# 1-Schematic_Placa_Final_ALS.net
KiCad netlist of a schematic drawn in EasyEDA
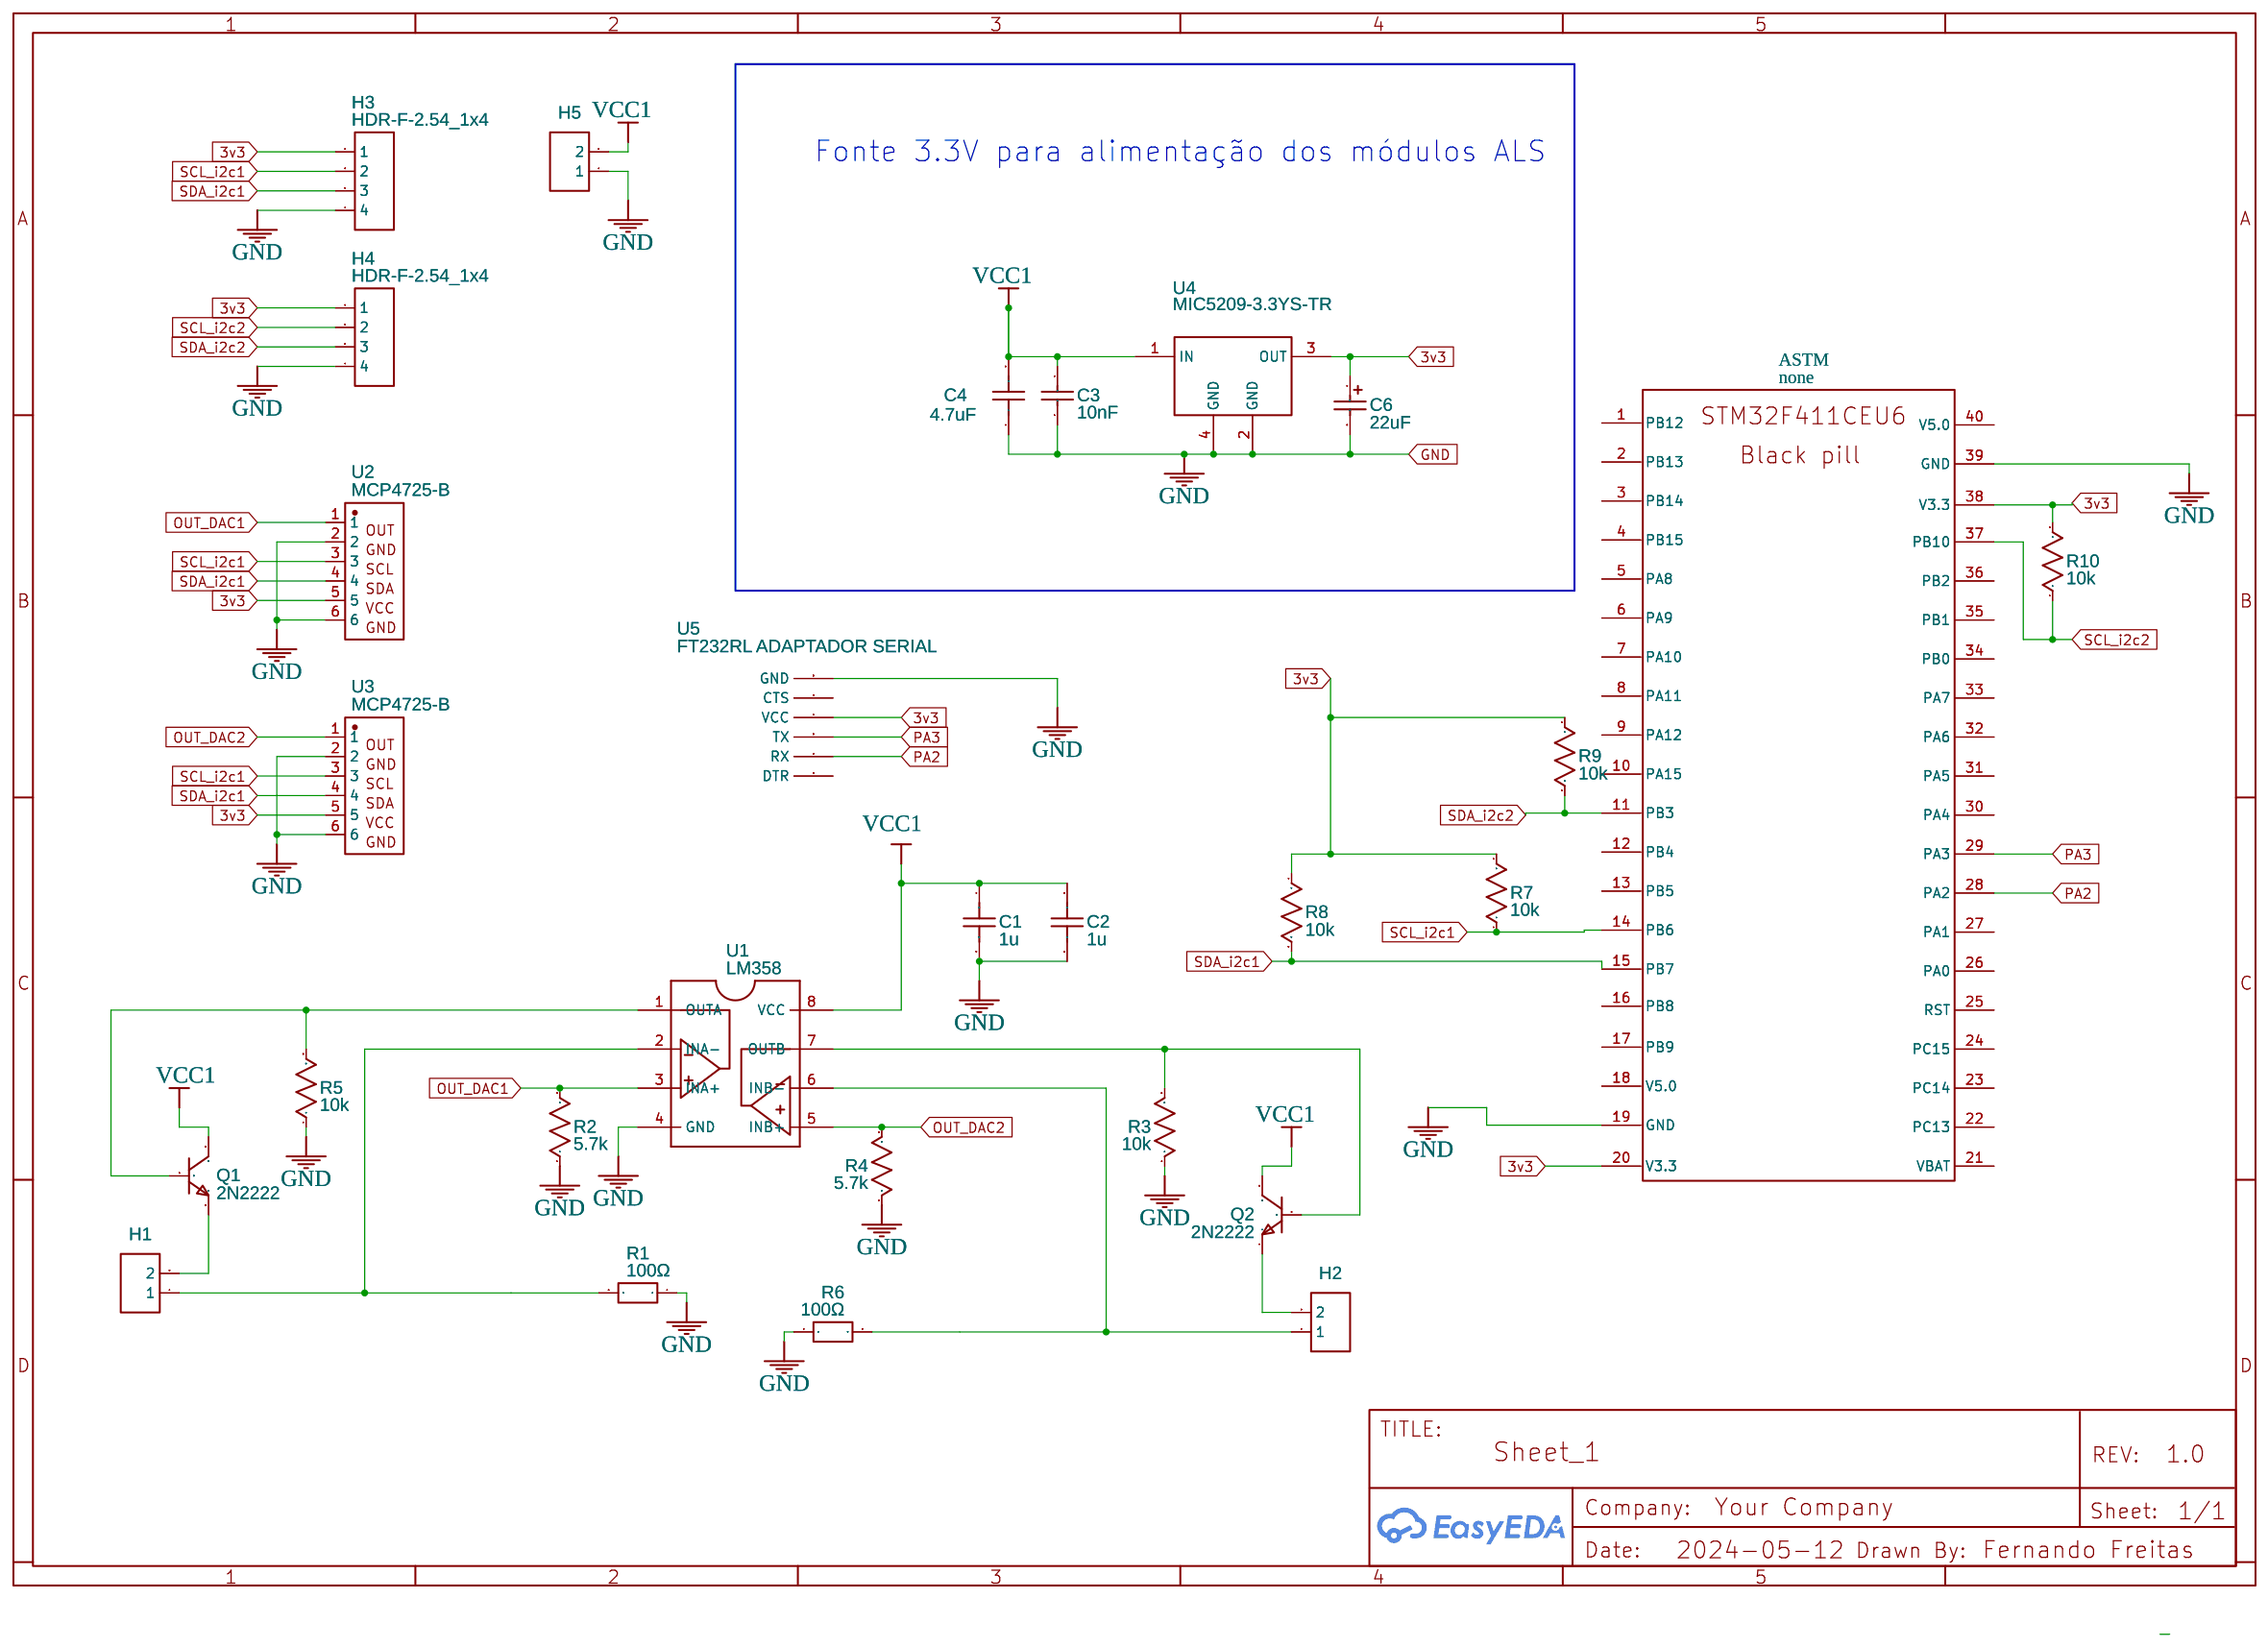
[diagram p0: schematic sheet]

(export (version "E")
  (design (tool "Eeschema 10.0.6"))
  (components
    (comp (ref "ASTM") (value "none") (libsource (lib "") (part "Unknown_912_-407")))
    (comp (ref "C1") (value "1u") (libsource (lib "") (part "C_RAD-0.3_US")))
    (comp (ref "C2") (value "1u") (libsource (lib "") (part "C_RAD-0.3_US")))
    (comp (ref "C3")
      (value "10nF")
      (fields
        (field (name "Manufacturer Part") "CL21B103KBANNNC")
        (field (name "Manufacturer") "SAMSUNG(三星)")
      )
      (libsource (lib "") (part "CL21B103KBANNNC"))
    )
    (comp (ref "C4")
      (value "4.7uF")
      (fields (field (name "Manufacturer Part") "CGA3E2X8R1E104M080AA") (field (name "Manufacturer") "TDK"))
      (libsource (lib "") (part "CGA3E2X8R1E104M080 AA"))
    )
    (comp (ref "C6")
      (value "22uF")
      (fields (field (name "Manufacturer Part") "TAJB226K016RNJ") (field (name "Manufacturer") "Kyocera AVX"))
      (libsource (lib "") (part "TAJB226K016RNJ"))
    )
    (comp (ref "H1") (value "HDR-F-2.54_1x2") (libsource (lib "") (part "HDR-F-2.54_1x2")))
    (comp (ref "H2") (value "HDR-F-2.54_1x2") (libsource (lib "") (part "HDR-F-2.54_1x2_1")))
    (comp (ref "H3") (value "HDR-F-2.54_1x4") (libsource (lib "") (part "HDR-F-2.54_1x4")))
    (comp (ref "H4") (value "HDR-F-2.54_1x4") (libsource (lib "") (part "HDR-F-2.54_1x4")))
    (comp (ref "H5") (value "HDR-F-2.54_1x2") (libsource (lib "") (part "HDR-F-2.54_1x2")))
    (comp (ref "Q1")
      (value "2N2222")
      (fields (field (name "Manufacturer Part") "2N2222A") (field (name "Manufacturer") "ST(先科)"))
      (libsource (lib "") (part "2N2222"))
    )
    (comp (ref "Q2")
      (value "2N2222")
      (fields (field (name "Manufacturer Part") "2N2222A") (field (name "Manufacturer") "ST(先科)"))
      (libsource (lib "") (part "2N2222_1"))
    )
    (comp (ref "R1")
      (value "100Ω")
      (fields
        (field (name "Manufacturer Part") "RN 1/4W 100R F T/B A1")
        (field (name "Manufacturer") "Tyohm(幸亚电阻)")
      )
      (libsource (lib "") (part "100R 1/4W_1"))
    )
    (comp (ref "R2") (value "5.7k") (libsource (lib "") (part "R_AXIAL-0.3_US")))
    (comp (ref "R3") (value "10k") (libsource (lib "") (part "R_AXIAL-0.3_US_1")))
    (comp (ref "R4") (value "5.7k") (libsource (lib "") (part "R_AXIAL-0.3_US_1")))
    (comp (ref "R5") (value "10k") (libsource (lib "") (part "R_AXIAL-0.3_US")))
    (comp (ref "R6")
      (value "100Ω")
      (fields
        (field (name "Manufacturer Part") "RN 1/4W 100R F T/B A1")
        (field (name "Manufacturer") "Tyohm(幸亚电阻)")
      )
      (libsource (lib "") (part "100R 1/4W"))
    )
    (comp (ref "R7") (value "10k") (libsource (lib "") (part "R_AXIAL-0.3_US")))
    (comp (ref "R8") (value "10k") (libsource (lib "") (part "R_AXIAL-0.3_US_2")))
    (comp (ref "R9") (value "10k") (libsource (lib "") (part "R_AXIAL-0.3_US_2")))
    (comp (ref "R10") (value "10k") (libsource (lib "") (part "R_AXIAL-0.3_US")))
    (comp (ref "U1")
      (value "LM358")
      (fields (field (name "Manufacturer Part") "TI") (field (name "Manufacturer") "LM358MX/NOPB"))
      (libsource (lib "") (part "LM358"))
    )
    (comp (ref "U2")
      (value "MCP4725-B")
      (fields
        (field (name "Manufacturer Part") "A2005WV-6P")
        (field (name "Manufacturer") "Changjiang Connectors")
      )
      (libsource (lib "") (part "MCP4725-B"))
    )
    (comp (ref "U3")
      (value "MCP4725-B")
      (fields
        (field (name "Manufacturer Part") "A2005WV-6P")
        (field (name "Manufacturer") "Changjiang Connectors")
      )
      (libsource (lib "") (part "MCP4725-B"))
    )
    (comp (ref "U4")
      (value "MIC5209-3.3YS-TR")
      (fields
        (field (name "Manufacturer Part") "TLE42744GSV33")
        (field (name "Manufacturer") "Infineon(英飞凌)")
      )
      (libsource (lib "") (part "TLE42744GSV33"))
    )
    (comp (ref "U5")
      (value "FT232RL ADAPTADOR SERIAL")
      (fields (field (name "Manufacturer Part") "WILSON") (field (name "Manufacturer") "WILSON PEREZ"))
      (libsource (lib "") (part "FT232RL ADAPTADOR SERIAL"))
    )
  )
  (nets
    (net (code "1") (name "3v3") (class "Default")
      (node (ref "ASTM") (pin "20") (pinfunction "V3.3_20") (pintype "passive"))
      (node (ref "ASTM") (pin "38") (pinfunction "V3.3_38") (pintype "passive"))
      (node (ref "C6") (pin "1") (pinfunction "1_1") (pintype "input"))
      (node (ref "H3") (pin "1") (pinfunction "1_1") (pintype "unspecified"))
      (node (ref "H4") (pin "1") (pinfunction "1_1") (pintype "unspecified"))
      (node (ref "R10") (pin "2") (pinfunction "2_2") (pintype "unspecified"))
      (node (ref "R7") (pin "2") (pinfunction "2_2") (pintype "unspecified"))
      (node (ref "R8") (pin "1") (pinfunction "1_1") (pintype "unspecified"))
      (node (ref "R9") (pin "1") (pinfunction "1_1") (pintype "unspecified"))
      (node (ref "U2") (pin "5") (pinfunction "5_5") (pintype "unspecified"))
      (node (ref "U3") (pin "5") (pinfunction "5_5") (pintype "unspecified"))
      (node (ref "U4") (pin "3") (pinfunction "OUT_3") (pintype "unspecified"))
      (node (ref "U5") (pin "4") (pinfunction "VCC_4") (pintype "unspecified"))
    )
    (net (code "2") (name "GND") (class "Default")
      (node (ref "ASTM") (pin "19") (pinfunction "GND_19") (pintype "passive"))
      (node (ref "ASTM") (pin "39") (pinfunction "GND_39") (pintype "passive"))
      (node (ref "C1") (pin "2") (pinfunction "2_2") (pintype "unspecified"))
      (node (ref "C2") (pin "2") (pinfunction "2_2") (pintype "unspecified"))
      (node (ref "C3") (pin "1") (pinfunction "1_1") (pintype "input"))
      (node (ref "C4") (pin "1") (pinfunction "1_1") (pintype "unspecified"))
      (node (ref "C6") (pin "2") (pinfunction "2_2") (pintype "input"))
      (node (ref "H3") (pin "4") (pinfunction "4_4") (pintype "unspecified"))
      (node (ref "H4") (pin "4") (pinfunction "4_4") (pintype "unspecified"))
      (node (ref "H5") (pin "1") (pinfunction "1_1") (pintype "input"))
      (node (ref "R1") (pin "1") (pinfunction "1_1") (pintype "unspecified"))
      (node (ref "R2") (pin "1") (pinfunction "1_1") (pintype "unspecified"))
      (node (ref "R3") (pin "1") (pinfunction "1_1") (pintype "unspecified"))
      (node (ref "R4") (pin "1") (pinfunction "1_1") (pintype "unspecified"))
      (node (ref "R5") (pin "1") (pinfunction "1_1") (pintype "unspecified"))
      (node (ref "R6") (pin "1") (pinfunction "1_1") (pintype "unspecified"))
      (node (ref "U1") (pin "4") (pinfunction "GND_4") (pintype "unspecified"))
      (node (ref "U2") (pin "2") (pinfunction "2_2") (pintype "unspecified"))
      (node (ref "U2") (pin "6") (pinfunction "6_6") (pintype "unspecified"))
      (node (ref "U3") (pin "2") (pinfunction "2_2") (pintype "unspecified"))
      (node (ref "U3") (pin "6") (pinfunction "6_6") (pintype "unspecified"))
      (node (ref "U4") (pin "2") (pinfunction "GND_2") (pintype "unspecified"))
      (node (ref "U4") (pin "4") (pinfunction "GND_4") (pintype "unspecified"))
      (node (ref "U5") (pin "6") (pinfunction "GND_6") (pintype "unspecified"))
    )
    (net (code "3") (name "Net-(Q1-B)") (class "Default")
      (node (ref "Q1") (pin "2") (pinfunction "B_2") (pintype "unspecified"))
      (node (ref "R5") (pin "2") (pinfunction "2_2") (pintype "unspecified"))
      (node (ref "U1") (pin "1") (pinfunction "OUTA_1") (pintype "output"))
    )
    (net (code "4") (name "Net-(Q1-E)") (class "Default")
      (node (ref "H1") (pin "2") (pinfunction "2_2") (pintype "input"))
      (node (ref "Q1") (pin "1") (pinfunction "E_1") (pintype "unspecified"))
    )
    (net (code "5") (name "Net-(Q2-B)") (class "Default")
      (node (ref "Q2") (pin "2") (pinfunction "B_2") (pintype "unspecified"))
      (node (ref "R3") (pin "2") (pinfunction "2_2") (pintype "unspecified"))
      (node (ref "U1") (pin "7") (pinfunction "OUTB_7") (pintype "unspecified"))
    )
    (net (code "6") (name "Net-(Q2-E)") (class "Default")
      (node (ref "H2") (pin "2") (pinfunction "2_2") (pintype "input"))
      (node (ref "Q2") (pin "1") (pinfunction "E_1") (pintype "unspecified"))
    )
    (net (code "7") (name "Net-(U1-INA-)") (class "Default")
      (node (ref "H1") (pin "1") (pinfunction "1_1") (pintype "input"))
      (node (ref "R1") (pin "2") (pinfunction "2_2") (pintype "unspecified"))
      (node (ref "U1") (pin "2") (pinfunction "INA-_2") (pintype "unspecified"))
    )
    (net (code "8") (name "Net-(U1-INB-)") (class "Default")
      (node (ref "H2") (pin "1") (pinfunction "1_1") (pintype "input"))
      (node (ref "R6") (pin "2") (pinfunction "2_2") (pintype "unspecified"))
      (node (ref "U1") (pin "6") (pinfunction "INB-_6") (pintype "unspecified"))
    )
    (net (code "9") (name "OUT_DAC1") (class "Default")
      (node (ref "R2") (pin "2") (pinfunction "2_2") (pintype "unspecified"))
      (node (ref "U1") (pin "3") (pinfunction "INA+_3") (pintype "unspecified"))
      (node (ref "U2") (pin "1") (pinfunction "1_1") (pintype "unspecified"))
    )
    (net (code "10") (name "OUT_DAC2") (class "Default")
      (node (ref "R4") (pin "2") (pinfunction "2_2") (pintype "unspecified"))
      (node (ref "U1") (pin "5") (pinfunction "INB+_5") (pintype "unspecified"))
      (node (ref "U3") (pin "1") (pinfunction "1_1") (pintype "unspecified"))
    )
    (net (code "11") (name "PA2") (class "Default")
      (node (ref "ASTM") (pin "28") (pinfunction "PA2_28") (pintype "unspecified"))
      (node (ref "U5") (pin "2") (pinfunction "RX_2") (pintype "unspecified"))
    )
    (net (code "12") (name "PA3") (class "Default")
      (node (ref "ASTM") (pin "29") (pinfunction "PA3_29") (pintype "unspecified"))
      (node (ref "U5") (pin "3") (pinfunction "TX_3") (pintype "unspecified"))
    )
    (net (code "13") (name "SCL_i2c1") (class "Default")
      (node (ref "ASTM") (pin "14") (pinfunction "PB6_14") (pintype "unspecified"))
      (node (ref "H3") (pin "2") (pinfunction "2_2") (pintype "unspecified"))
      (node (ref "R7") (pin "1") (pinfunction "1_1") (pintype "unspecified"))
      (node (ref "U2") (pin "3") (pinfunction "3_3") (pintype "unspecified"))
      (node (ref "U3") (pin "3") (pinfunction "3_3") (pintype "unspecified"))
    )
    (net (code "14") (name "SCL_i2c2") (class "Default")
      (node (ref "ASTM") (pin "37") (pinfunction "PB10_37") (pintype "unspecified"))
      (node (ref "H4") (pin "2") (pinfunction "2_2") (pintype "unspecified"))
      (node (ref "R10") (pin "1") (pinfunction "1_1") (pintype "unspecified"))
    )
    (net (code "15") (name "SDA_i2c1") (class "Default")
      (node (ref "ASTM") (pin "15") (pinfunction "PB7_15") (pintype "unspecified"))
      (node (ref "H3") (pin "3") (pinfunction "3_3") (pintype "unspecified"))
      (node (ref "R8") (pin "2") (pinfunction "2_2") (pintype "unspecified"))
      (node (ref "U2") (pin "4") (pinfunction "4_4") (pintype "unspecified"))
      (node (ref "U3") (pin "4") (pinfunction "4_4") (pintype "unspecified"))
    )
    (net (code "16") (name "SDA_i2c2") (class "Default")
      (node (ref "ASTM") (pin "11") (pinfunction "PB3_11") (pintype "unspecified"))
      (node (ref "H4") (pin "3") (pinfunction "3_3") (pintype "unspecified"))
      (node (ref "R9") (pin "2") (pinfunction "2_2") (pintype "unspecified"))
    )
    (net (code "17") (name "VCC1") (class "Default")
      (node (ref "C1") (pin "1") (pinfunction "1_1") (pintype "unspecified"))
      (node (ref "C2") (pin "1") (pinfunction "1_1") (pintype "unspecified"))
      (node (ref "C3") (pin "2") (pinfunction "2_2") (pintype "input"))
      (node (ref "C4") (pin "2") (pinfunction "2_2") (pintype "unspecified"))
      (node (ref "H5") (pin "2") (pinfunction "2_2") (pintype "input"))
      (node (ref "Q1") (pin "3") (pinfunction "C_3") (pintype "unspecified"))
      (node (ref "Q2") (pin "3") (pinfunction "C_3") (pintype "unspecified"))
      (node (ref "U1") (pin "8") (pinfunction "VCC_8") (pintype "unspecified"))
      (node (ref "U4") (pin "1") (pinfunction "IN_1") (pintype "unspecified"))
    )
    (net (code "18") (name "unconnected-(ASTM-PA0-Pad26)") (class "Default")
      (node (ref "ASTM") (pin "26") (pinfunction "PA0_26") (pintype "unspecified"))
    )
    (net (code "19") (name "unconnected-(ASTM-PA1-Pad27)") (class "Default")
      (node (ref "ASTM") (pin "27") (pinfunction "PA1_27") (pintype "unspecified"))
    )
    (net (code "20") (name "unconnected-(ASTM-PA4-Pad30)") (class "Default")
      (node (ref "ASTM") (pin "30") (pinfunction "PA4_30") (pintype "unspecified"))
    )
    (net (code "21") (name "unconnected-(ASTM-PA5-Pad31)") (class "Default")
      (node (ref "ASTM") (pin "31") (pinfunction "PA5_31") (pintype "unspecified"))
    )
    (net (code "22") (name "unconnected-(ASTM-PA6-Pad32)") (class "Default")
      (node (ref "ASTM") (pin "32") (pinfunction "PA6_32") (pintype "unspecified"))
    )
    (net (code "23") (name "unconnected-(ASTM-PA7-Pad33)") (class "Default")
      (node (ref "ASTM") (pin "33") (pinfunction "PA7_33") (pintype "unspecified"))
    )
    (net (code "24") (name "unconnected-(ASTM-PA8-Pad5)") (class "Default")
      (node (ref "ASTM") (pin "5") (pinfunction "PA8_5") (pintype "unspecified"))
    )
    (net (code "25") (name "unconnected-(ASTM-PA9-Pad6)") (class "Default")
      (node (ref "ASTM") (pin "6") (pinfunction "PA9_6") (pintype "unspecified"))
    )
    (net (code "26") (name "unconnected-(ASTM-PA10-Pad7)") (class "Default")
      (node (ref "ASTM") (pin "7") (pinfunction "PA10_7") (pintype "unspecified"))
    )
    (net (code "27") (name "unconnected-(ASTM-PA11-Pad8)") (class "Default")
      (node (ref "ASTM") (pin "8") (pinfunction "PA11_8") (pintype "unspecified"))
    )
    (net (code "28") (name "unconnected-(ASTM-PA12-Pad9)") (class "Default")
      (node (ref "ASTM") (pin "9") (pinfunction "PA12_9") (pintype "unspecified"))
    )
    (net (code "29") (name "unconnected-(ASTM-PA15-Pad10)") (class "Default")
      (node (ref "ASTM") (pin "10") (pinfunction "PA15_10") (pintype "unspecified"))
    )
    (net (code "30") (name "unconnected-(ASTM-PB0-Pad34)") (class "Default")
      (node (ref "ASTM") (pin "34") (pinfunction "PB0_34") (pintype "unspecified"))
    )
    (net (code "31") (name "unconnected-(ASTM-PB1-Pad35)") (class "Default")
      (node (ref "ASTM") (pin "35") (pinfunction "PB1_35") (pintype "unspecified"))
    )
    (net (code "32") (name "unconnected-(ASTM-PB2-Pad36)") (class "Default")
      (node (ref "ASTM") (pin "36") (pinfunction "PB2_36") (pintype "unspecified"))
    )
    (net (code "33") (name "unconnected-(ASTM-PB4-Pad12)") (class "Default")
      (node (ref "ASTM") (pin "12") (pinfunction "PB4_12") (pintype "unspecified"))
    )
    (net (code "34") (name "unconnected-(ASTM-PB5-Pad13)") (class "Default")
      (node (ref "ASTM") (pin "13") (pinfunction "PB5_13") (pintype "unspecified"))
    )
    (net (code "35") (name "unconnected-(ASTM-PB8-Pad16)") (class "Default")
      (node (ref "ASTM") (pin "16") (pinfunction "PB8_16") (pintype "unspecified"))
    )
    (net (code "36") (name "unconnected-(ASTM-PB9-Pad17)") (class "Default")
      (node (ref "ASTM") (pin "17") (pinfunction "PB9_17") (pintype "unspecified"))
    )
    (net (code "37") (name "unconnected-(ASTM-PB12-Pad1)") (class "Default")
      (node (ref "ASTM") (pin "1") (pinfunction "PB12_1") (pintype "unspecified"))
    )
    (net (code "38") (name "unconnected-(ASTM-PB13-Pad2)") (class "Default")
      (node (ref "ASTM") (pin "2") (pinfunction "PB13_2") (pintype "unspecified"))
    )
    (net (code "39") (name "unconnected-(ASTM-PB14-Pad3)") (class "Default")
      (node (ref "ASTM") (pin "3") (pinfunction "PB14_3") (pintype "unspecified"))
    )
    (net (code "40") (name "unconnected-(ASTM-PB15-Pad4)") (class "Default")
      (node (ref "ASTM") (pin "4") (pinfunction "PB15_4") (pintype "unspecified"))
    )
    (net (code "41") (name "unconnected-(ASTM-PC13-Pad22)") (class "Default")
      (node (ref "ASTM") (pin "22") (pinfunction "PC13_22") (pintype "unspecified"))
    )
    (net (code "42") (name "unconnected-(ASTM-PC14-Pad23)") (class "Default")
      (node (ref "ASTM") (pin "23") (pinfunction "PC14_23") (pintype "unspecified"))
    )
    (net (code "43") (name "unconnected-(ASTM-PC15-Pad24)") (class "Default")
      (node (ref "ASTM") (pin "24") (pinfunction "PC15_24") (pintype "unspecified"))
    )
    (net (code "44") (name "unconnected-(ASTM-RST-Pad25)") (class "Default")
      (node (ref "ASTM") (pin "25") (pinfunction "RST_25") (pintype "unspecified"))
    )
    (net (code "45") (name "unconnected-(ASTM-V5.0-Pad18)") (class "Default")
      (node (ref "ASTM") (pin "18") (pinfunction "V5.0_18") (pintype "passive"))
    )
    (net (code "46") (name "unconnected-(ASTM-V5.0-Pad40)") (class "Default")
      (node (ref "ASTM") (pin "40") (pinfunction "V5.0_40") (pintype "passive"))
    )
    (net (code "47") (name "unconnected-(ASTM-VBAT-Pad21)") (class "Default")
      (node (ref "ASTM") (pin "21") (pinfunction "VBAT_21") (pintype "passive"))
    )
    (net (code "48") (name "unconnected-(U5-CTS-Pad5)") (class "Default")
      (node (ref "U5") (pin "5") (pinfunction "CTS_5") (pintype "unspecified"))
    )
    (net (code "49") (name "unconnected-(U5-DTR-Pad1)") (class "Default")
      (node (ref "U5") (pin "1") (pinfunction "DTR_1") (pintype "unspecified"))
    )
  )
)
